# design.net
KiCad netlist of a schematic drawn in EasyEDA Pro
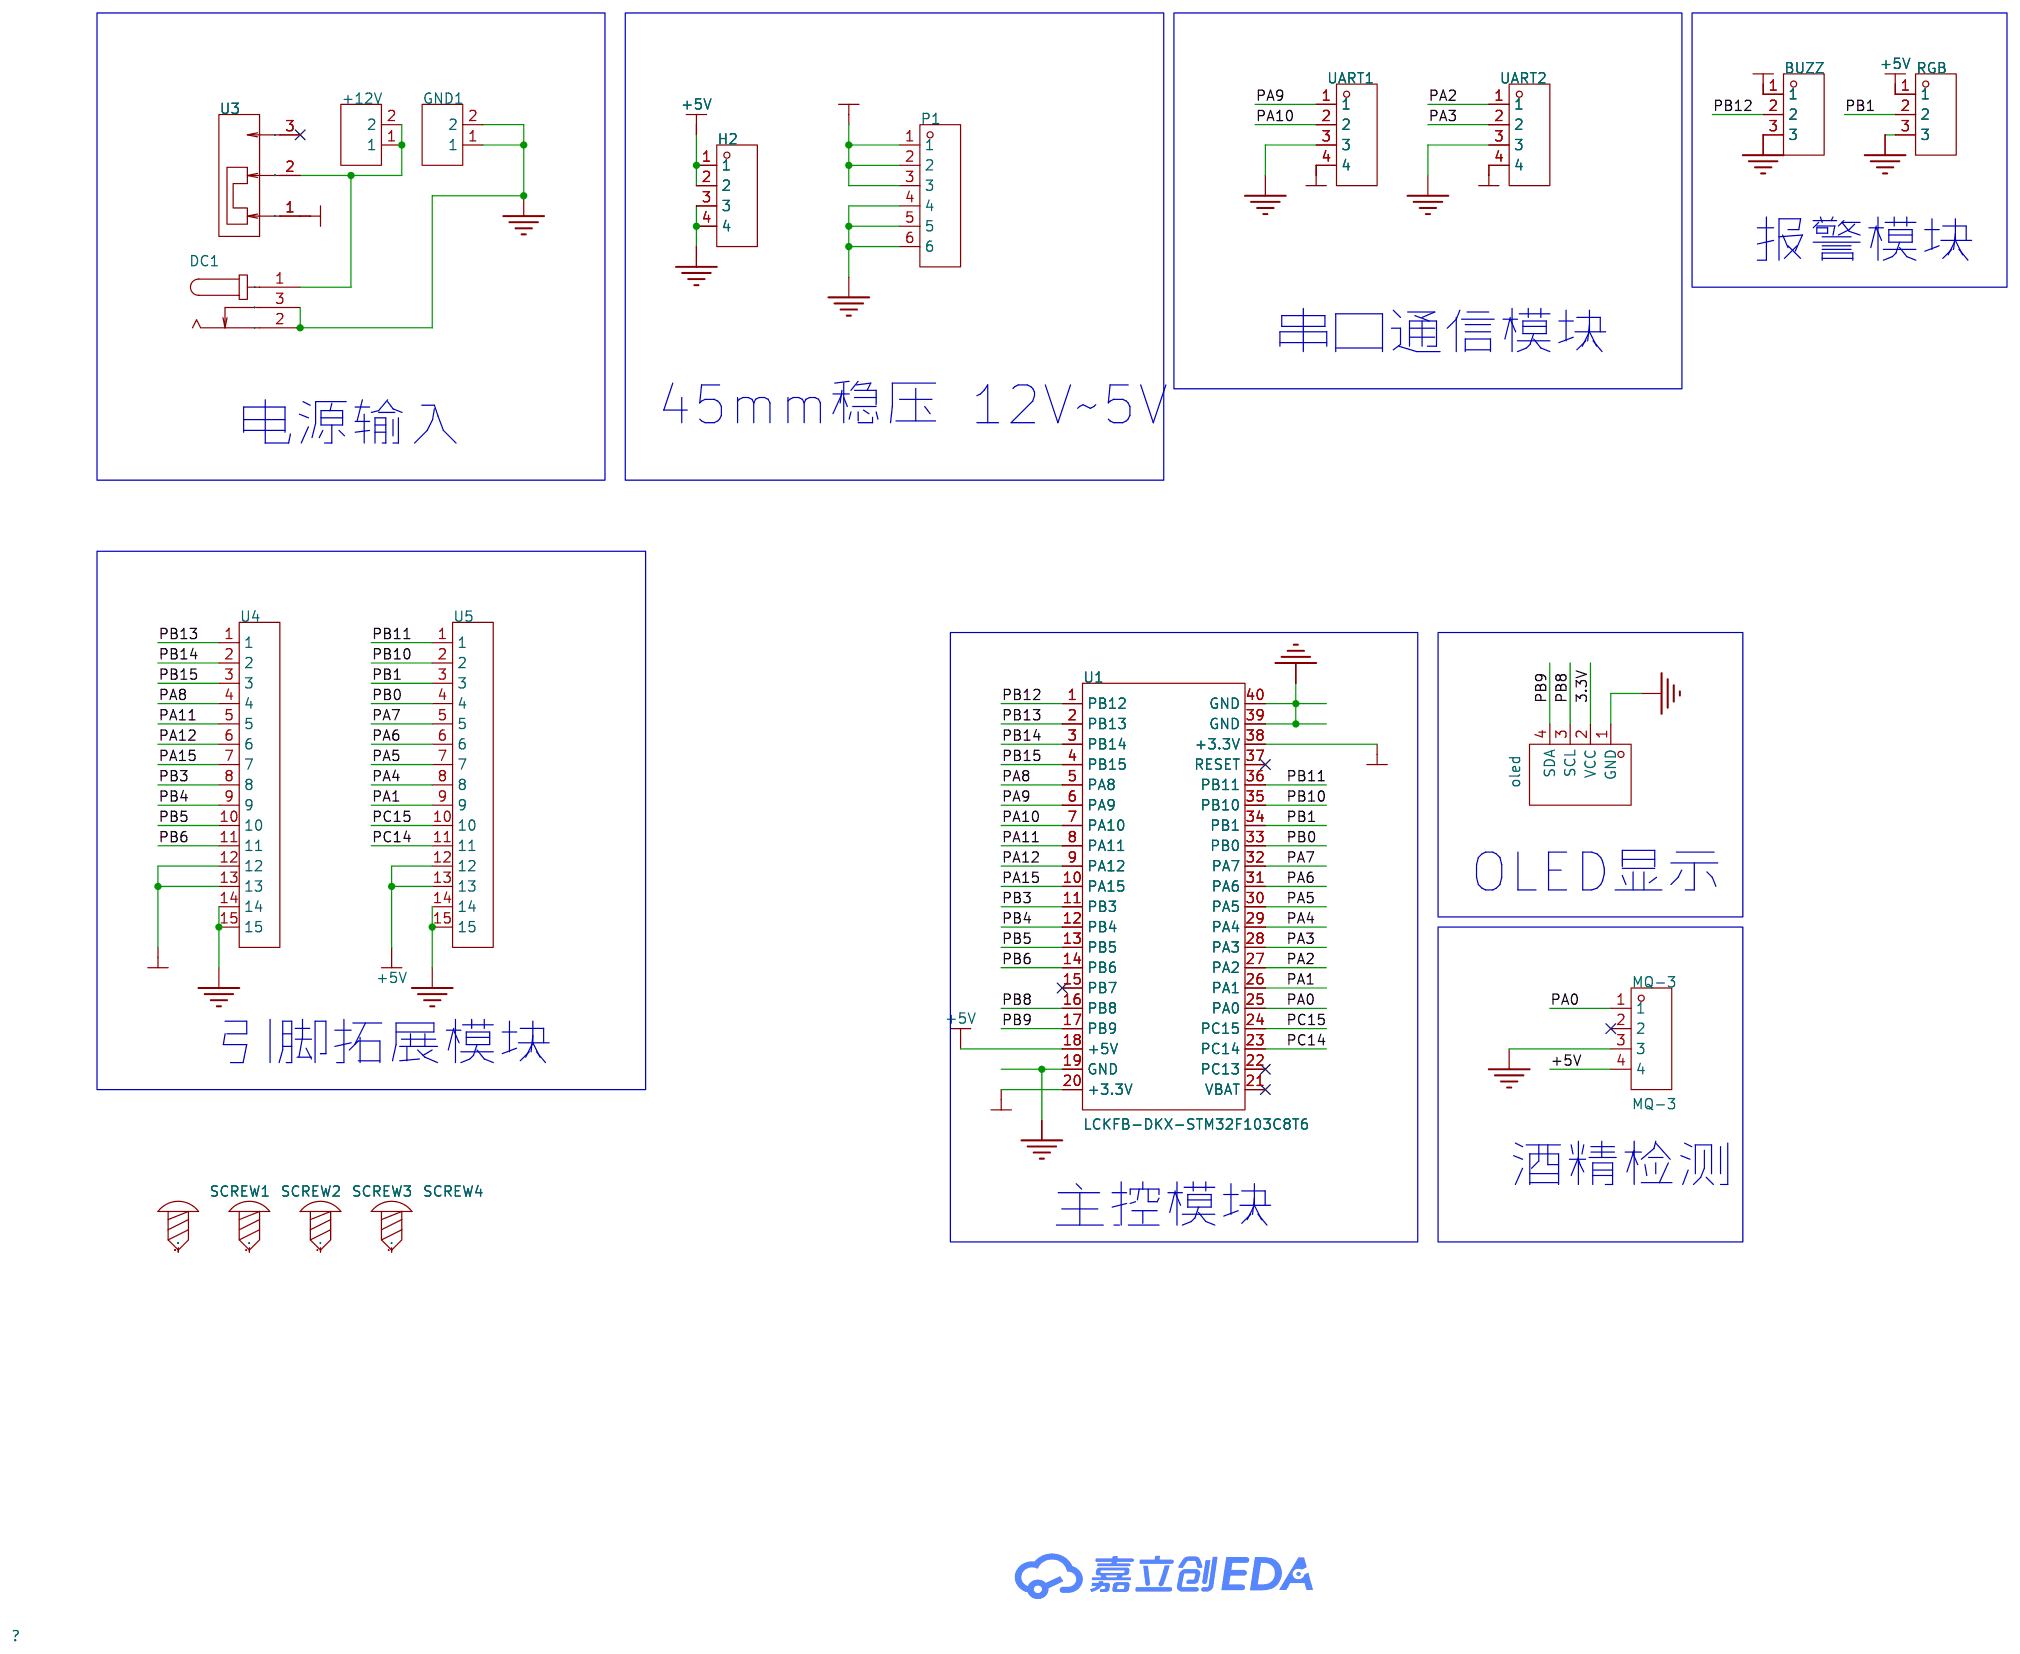
[diagram p0: schematic sheet]

(export (version "E")
  (design (tool "Eeschema 10.0.6"))
  (components
    (comp (ref "+12V")
      (value "Z-211-0211-0021-001")
      (footprint "easyedapro:HDR-TH_2P-P2.54-V-M-1")
      (fields (field (name "Manufacturer") "Nextron(正凌)"))
      (libsource (lib "easyedapro") (part "Z-211-0211-0021-001"))
    )
    (comp (ref "BUZZ")
      (value "HC-PM254-8.5H-1x3PZ-02A")
      (footprint "easyedapro:HDR-TH_3P-P2.54-V-F")
      (fields (field (name "Manufacturer") "HC(虹成电子)"))
      (libsource (lib "easyedapro") (part "HC-PM254-8.5H-1X3PZ"))
    )
    (comp (ref "DC1")
      (value "DC005-T")
      (footprint "easyedapro:DC-IN-TH_DC005-T")
      (description "连接器类型:DC电源插座;安装方式:弯插;触点内径:2mm;触点外径:6.3mm;额定电流:1.5A;额定电压:12V;工作温度:-30°C~+70°C;")
      (fields (field (name "Manufacturer") "SHOU HAN(首韩)"))
      (libsource (lib "easyedapro") (part "DC005-T"))
    )
    (comp (ref "GND1")
      (value "Z-211-0211-0021-001")
      (footprint "easyedapro:HDR-TH_2P-P2.54-V-M-1")
      (fields (field (name "Manufacturer") "Nextron(正凌)"))
      (libsource (lib "easyedapro") (part "Z-211-0211-0021-001"))
    )
    (comp (ref "H2")
      (value "2.54-1*4P母")
      (footprint "easyedapro:HDR-TH_4P-P2.54-V-F")
      (fields (field (name "Manufacturer") "BOOMELE(博穆精密)"))
      (libsource (lib "easyedapro") (part "2.54-1*4P母"))
    )
    (comp (ref "MQ-3")
      (value "MQ-3")
      (footprint "easyedapro:HDR-TH_4P-P2.54-V-F")
      (fields (field (name "Manufacturer") "XFCN(兴飞)"))
      (libsource (lib "easyedapro") (part "PM254V-11-04-H85"))
    )
    (comp (ref "oled")
      (value "HS96L03W2C03")
      (footprint "easyedapro:OLED-TH_L27.8-W27.2-P2.54_C9900033791")
      (description "主控芯片:SSD1315;接口类型:I2C;尺寸(inch):0.96;像素分辨率:128x64;")
      (fields (field (name "Manufacturer") "HS(汉昇)"))
      (libsource (lib "easyedapro") (part "HS96L03W2C03"))
    )
    (comp (ref "P1")
      (value "2.54-1*6P母")
      (footprint "easyedapro:HDR-TH_6P-P2.54-V-F")
      (fields (field (name "Manufacturer") "BOOMELE(博穆精密)"))
      (libsource (lib "easyedapro") (part "Header-Female-2.54_1x6"))
    )
    (comp (ref "RGB")
      (value "HC-PM254-8.5H-1x3PZ-02A")
      (footprint "easyedapro:HDR-TH_3P-P2.54-V-F")
      (fields (field (name "Manufacturer") "HC(虹成电子)"))
      (libsource (lib "easyedapro") (part "HC-PM254-8.5H-1X3PZ"))
    )
    (comp (ref "SCREW1")
      (value "~")
      (footprint "easyedapro:M2螺丝")
      (libsource (lib "easyedapro") (part "螺丝孔"))
    )
    (comp (ref "SCREW2")
      (value "~")
      (footprint "easyedapro:M2螺丝")
      (libsource (lib "easyedapro") (part "螺丝孔"))
    )
    (comp (ref "SCREW3")
      (value "~")
      (footprint "easyedapro:M2螺丝")
      (libsource (lib "easyedapro") (part "螺丝孔"))
    )
    (comp (ref "SCREW4")
      (value "~")
      (footprint "easyedapro:M2螺丝")
      (libsource (lib "easyedapro") (part "螺丝孔"))
    )
    (comp (ref "U1")
      (value "LCKFB-DKX-STM32F103C8T6")
      (footprint "easyedapro:CONN-TH_L53.3-W22.9_STM32F103C8T6-CARD")
      (description "搭载Contex M3内核,程序存储容量64KB,RAM总容量20KB,最高72MHz主频,提供高效的计算能力和稳定的运行环境。")
      (fields (field (name "Manufacturer") "立创开发板"))
      (libsource (lib "easyedapro") (part "LCKFB-DKX-STM32F103C8T6"))
    )
    (comp (ref "U3")
      (value "SS-12D10-G5")
      (footprint "easyedapro:SW-TH_SS-12D10-G050")
      (description "电路结构:单刀双掷;安装方式:直插;开关颜色:黑色;工作寿命:-;")
      (fields (field (name "Manufacturer") "DEALON(德艺隆)"))
      (libsource (lib "easyedapro") (part "SS-12D10-G5"))
    )
    (comp (ref "U4")
      (value "ZX-PZ2.54-1-15PZZ")
      (footprint "easyedapro:HDR-TH_15P-P2.54-V-M")
      (fields (field (name "Manufacturer") "Megastar(兆星)"))
      (libsource (lib "easyedapro") (part "ZX-PZ2.54-1-15PZZ"))
    )
    (comp (ref "U5")
      (value "ZX-PZ2.54-1-15PZZ")
      (footprint "easyedapro:HDR-TH_15P-P2.54-V-M")
      (fields (field (name "Manufacturer") "Megastar(兆星)"))
      (libsource (lib "easyedapro") (part "ZX-PZ2.54-1-15PZZ"))
    )
    (comp (ref "UART1")
      (value "PZ254V-11-04P")
      (footprint "easyedapro:HDR-TH_4P-P2.54-V-M")
      (fields (field (name "Manufacturer") "XFCN(兴飞)"))
      (libsource (lib "easyedapro") (part "PZ254V-11-04P_C2691448"))
    )
    (comp (ref "UART2")
      (value "PZ254V-11-04P")
      (footprint "easyedapro:HDR-TH_4P-P2.54-V-M")
      (fields (field (name "Manufacturer") "XFCN(兴飞)"))
      (libsource (lib "easyedapro") (part "PZ254V-11-04P_C2691448"))
    )
  )
  (nets
    (net (code "1") (name "+5V") (class "Default")
      (node (ref "H2") (pin "1") (pinfunction "1_1") (pintype "unspecified"))
      (node (ref "H2") (pin "2") (pinfunction "2_2") (pintype "unspecified"))
      (node (ref "MQ-3") (pin "4") (pinfunction "4_4") (pintype "unspecified"))
      (node (ref "RGB") (pin "1") (pinfunction "1_1") (pintype "unspecified"))
      (node (ref "U1") (pin "18") (pinfunction "+5V_18") (pintype "unspecified"))
      (node (ref "U5") (pin "12") (pinfunction "12_12") (pintype "unspecified"))
      (node (ref "U5") (pin "13") (pinfunction "13_13") (pintype "unspecified"))
    )
    (net (code "2") (name "+12V") (class "Default")
      (node (ref "P1") (pin "1") (pinfunction "1_1") (pintype "unspecified"))
      (node (ref "P1") (pin "2") (pinfunction "2_2") (pintype "unspecified"))
      (node (ref "P1") (pin "3") (pinfunction "3_3") (pintype "unspecified"))
      (node (ref "U3") (pin "1") (pinfunction "1_1") (pintype "unspecified"))
    )
    (net (code "3") (name "/PA0") (class "Default")
      (node (ref "MQ-3") (pin "1") (pinfunction "1_1") (pintype "unspecified"))
      (node (ref "U1") (pin "25") (pinfunction "PA0_25") (pintype "unspecified"))
    )
    (net (code "4") (name "/PA1") (class "Default")
      (node (ref "U1") (pin "26") (pinfunction "PA1_26") (pintype "unspecified"))
      (node (ref "U5") (pin "9") (pinfunction "9_9") (pintype "unspecified"))
    )
    (net (code "5") (name "/PA2") (class "Default")
      (node (ref "U1") (pin "27") (pinfunction "PA2_27") (pintype "unspecified"))
      (node (ref "UART2") (pin "1") (pinfunction "1_1") (pintype "unspecified"))
    )
    (net (code "6") (name "/PA3") (class "Default")
      (node (ref "U1") (pin "28") (pinfunction "PA3_28") (pintype "unspecified"))
      (node (ref "UART2") (pin "2") (pinfunction "2_2") (pintype "unspecified"))
    )
    (net (code "7") (name "/PA4") (class "Default")
      (node (ref "U1") (pin "29") (pinfunction "PA4_29") (pintype "unspecified"))
      (node (ref "U5") (pin "8") (pinfunction "8_8") (pintype "unspecified"))
    )
    (net (code "8") (name "/PA5") (class "Default")
      (node (ref "U1") (pin "30") (pinfunction "PA5_30") (pintype "unspecified"))
      (node (ref "U5") (pin "7") (pinfunction "7_7") (pintype "unspecified"))
    )
    (net (code "9") (name "/PA6") (class "Default")
      (node (ref "U1") (pin "31") (pinfunction "PA6_31") (pintype "unspecified"))
      (node (ref "U5") (pin "6") (pinfunction "6_6") (pintype "unspecified"))
    )
    (net (code "10") (name "/PA7") (class "Default")
      (node (ref "U1") (pin "32") (pinfunction "PA7_32") (pintype "unspecified"))
      (node (ref "U5") (pin "5") (pinfunction "5_5") (pintype "unspecified"))
    )
    (net (code "11") (name "/PA8") (class "Default")
      (node (ref "U1") (pin "5") (pinfunction "PA8_5") (pintype "unspecified"))
      (node (ref "U4") (pin "4") (pinfunction "4_4") (pintype "unspecified"))
    )
    (net (code "12") (name "/PA9") (class "Default")
      (node (ref "U1") (pin "6") (pinfunction "PA9_6") (pintype "unspecified"))
      (node (ref "UART1") (pin "1") (pinfunction "1_1") (pintype "unspecified"))
    )
    (net (code "13") (name "/PA10") (class "Default")
      (node (ref "U1") (pin "7") (pinfunction "PA10_7") (pintype "unspecified"))
      (node (ref "UART1") (pin "2") (pinfunction "2_2") (pintype "unspecified"))
    )
    (net (code "14") (name "/PA11") (class "Default")
      (node (ref "U1") (pin "8") (pinfunction "PA11_8") (pintype "unspecified"))
      (node (ref "U4") (pin "5") (pinfunction "5_5") (pintype "unspecified"))
    )
    (net (code "15") (name "/PA12") (class "Default")
      (node (ref "U1") (pin "9") (pinfunction "PA12_9") (pintype "unspecified"))
      (node (ref "U4") (pin "6") (pinfunction "6_6") (pintype "unspecified"))
    )
    (net (code "16") (name "/PA15") (class "Default")
      (node (ref "U1") (pin "10") (pinfunction "PA15_10") (pintype "unspecified"))
      (node (ref "U4") (pin "7") (pinfunction "7_7") (pintype "unspecified"))
    )
    (net (code "17") (name "/PB0") (class "Default")
      (node (ref "U1") (pin "33") (pinfunction "PB0_33") (pintype "unspecified"))
      (node (ref "U5") (pin "4") (pinfunction "4_4") (pintype "unspecified"))
    )
    (net (code "18") (name "/PB1") (class "Default")
      (node (ref "RGB") (pin "2") (pinfunction "2_2") (pintype "unspecified"))
      (node (ref "U1") (pin "34") (pinfunction "PB1_34") (pintype "unspecified"))
      (node (ref "U5") (pin "3") (pinfunction "3_3") (pintype "unspecified"))
    )
    (net (code "19") (name "/PB3") (class "Default")
      (node (ref "U1") (pin "11") (pinfunction "PB3_11") (pintype "unspecified"))
      (node (ref "U4") (pin "8") (pinfunction "8_8") (pintype "unspecified"))
    )
    (net (code "20") (name "/PB4") (class "Default")
      (node (ref "U1") (pin "12") (pinfunction "PB4_12") (pintype "unspecified"))
      (node (ref "U4") (pin "9") (pinfunction "9_9") (pintype "unspecified"))
    )
    (net (code "21") (name "/PB5") (class "Default")
      (node (ref "U1") (pin "13") (pinfunction "PB5_13") (pintype "unspecified"))
      (node (ref "U4") (pin "10") (pinfunction "10_10") (pintype "unspecified"))
    )
    (net (code "22") (name "/PB6") (class "Default")
      (node (ref "U1") (pin "14") (pinfunction "PB6_14") (pintype "unspecified"))
      (node (ref "U4") (pin "11") (pinfunction "11_11") (pintype "unspecified"))
    )
    (net (code "23") (name "/PB8") (class "Default")
      (node (ref "U1") (pin "16") (pinfunction "PB8_16") (pintype "unspecified"))
      (node (ref "oled") (pin "3") (pinfunction "SCL_3") (pintype "unspecified"))
    )
    (net (code "24") (name "/PB9") (class "Default")
      (node (ref "U1") (pin "17") (pinfunction "PB9_17") (pintype "unspecified"))
      (node (ref "oled") (pin "4") (pinfunction "SDA_4") (pintype "unspecified"))
    )
    (net (code "25") (name "/PB10") (class "Default")
      (node (ref "U1") (pin "35") (pinfunction "PB10_35") (pintype "unspecified"))
      (node (ref "U5") (pin "2") (pinfunction "2_2") (pintype "unspecified"))
    )
    (net (code "26") (name "/PB11") (class "Default")
      (node (ref "U1") (pin "36") (pinfunction "PB11_36") (pintype "unspecified"))
      (node (ref "U5") (pin "1") (pinfunction "1_1") (pintype "unspecified"))
    )
    (net (code "27") (name "/PB12") (class "Default")
      (node (ref "BUZZ") (pin "2") (pinfunction "2_2") (pintype "unspecified"))
      (node (ref "U1") (pin "1") (pinfunction "PB12_1") (pintype "unspecified"))
    )
    (net (code "28") (name "/PB13") (class "Default")
      (node (ref "U1") (pin "2") (pinfunction "PB13_2") (pintype "unspecified"))
      (node (ref "U4") (pin "1") (pinfunction "1_1") (pintype "unspecified"))
    )
    (net (code "29") (name "/PB14") (class "Default")
      (node (ref "U1") (pin "3") (pinfunction "PB14_3") (pintype "unspecified"))
      (node (ref "U4") (pin "2") (pinfunction "2_2") (pintype "unspecified"))
    )
    (net (code "30") (name "/PB15") (class "Default")
      (node (ref "U1") (pin "4") (pinfunction "PB15_4") (pintype "unspecified"))
      (node (ref "U4") (pin "3") (pinfunction "3_3") (pintype "unspecified"))
    )
    (net (code "31") (name "/PC14") (class "Default")
      (node (ref "U1") (pin "23") (pinfunction "PC14_23") (pintype "unspecified"))
      (node (ref "U5") (pin "11") (pinfunction "11_11") (pintype "unspecified"))
    )
    (net (code "32") (name "/PC15") (class "Default")
      (node (ref "U1") (pin "24") (pinfunction "PC15_24") (pintype "unspecified"))
      (node (ref "U5") (pin "10") (pinfunction "10_10") (pintype "unspecified"))
    )
    (net (code "33") (name "3.3V") (class "Default")
      (node (ref "BUZZ") (pin "1") (pinfunction "1_1") (pintype "unspecified"))
      (node (ref "U1") (pin "20") (pinfunction "+3.3V_20") (pintype "unspecified"))
      (node (ref "U1") (pin "38") (pinfunction "+3.3V_38") (pintype "unspecified"))
      (node (ref "U4") (pin "12") (pinfunction "12_12") (pintype "unspecified"))
      (node (ref "U4") (pin "13") (pinfunction "13_13") (pintype "unspecified"))
      (node (ref "UART1") (pin "4") (pinfunction "4_4") (pintype "unspecified"))
      (node (ref "UART2") (pin "4") (pinfunction "4_4") (pintype "unspecified"))
      (node (ref "oled") (pin "2") (pinfunction "VCC_2") (pintype "unspecified"))
    )
    (net (code "34") (name "GND") (class "Default")
      (node (ref "BUZZ") (pin "3") (pinfunction "3_3") (pintype "unspecified"))
      (node (ref "DC1") (pin "2") (pinfunction "2_2") (pintype "unspecified"))
      (node (ref "DC1") (pin "3") (pinfunction "3_3") (pintype "unspecified"))
      (node (ref "GND1") (pin "1") (pinfunction "1_1") (pintype "unspecified"))
      (node (ref "GND1") (pin "2") (pinfunction "2_2") (pintype "unspecified"))
      (node (ref "H2") (pin "3") (pinfunction "3_3") (pintype "unspecified"))
      (node (ref "H2") (pin "4") (pinfunction "4_4") (pintype "unspecified"))
      (node (ref "MQ-3") (pin "3") (pinfunction "3_3") (pintype "unspecified"))
      (node (ref "P1") (pin "4") (pinfunction "4_4") (pintype "unspecified"))
      (node (ref "P1") (pin "5") (pinfunction "5_5") (pintype "unspecified"))
      (node (ref "P1") (pin "6") (pinfunction "6_6") (pintype "unspecified"))
      (node (ref "RGB") (pin "3") (pinfunction "3_3") (pintype "unspecified"))
      (node (ref "U1") (pin "19") (pinfunction "GND_19") (pintype "unspecified"))
      (node (ref "U1") (pin "39") (pinfunction "GND_39") (pintype "unspecified"))
      (node (ref "U1") (pin "40") (pinfunction "GND_40") (pintype "unspecified"))
      (node (ref "U4") (pin "14") (pinfunction "14_14") (pintype "unspecified"))
      (node (ref "U4") (pin "15") (pinfunction "15_15") (pintype "unspecified"))
      (node (ref "U5") (pin "14") (pinfunction "14_14") (pintype "unspecified"))
      (node (ref "U5") (pin "15") (pinfunction "15_15") (pintype "unspecified"))
      (node (ref "UART1") (pin "3") (pinfunction "3_3") (pintype "unspecified"))
      (node (ref "UART2") (pin "3") (pinfunction "3_3") (pintype "unspecified"))
      (node (ref "oled") (pin "1") (pinfunction "GND_1") (pintype "unspecified"))
    )
    (net (code "35") (name "Net-(+12V-Pad1)") (class "Default")
      (node (ref "+12V") (pin "1") (pinfunction "1_1") (pintype "unspecified"))
      (node (ref "+12V") (pin "2") (pinfunction "2_2") (pintype "unspecified"))
      (node (ref "DC1") (pin "1") (pinfunction "1_1") (pintype "unspecified"))
      (node (ref "U3") (pin "2") (pinfunction "2_2") (pintype "unspecified"))
    )
    (net (code "36") (name "unconnected-(MQ-3-Pad2)") (class "Default")
      (node (ref "MQ-3") (pin "2") (pinfunction "2_2") (pintype "unspecified+no_connect"))
    )
    (net (code "37") (name "unconnected-(SCREW1-Pad1)") (class "Default")
      (node (ref "SCREW1") (pin "1") (pinfunction "1_1") (pintype "input"))
    )
    (net (code "38") (name "unconnected-(SCREW2-Pad1)") (class "Default")
      (node (ref "SCREW2") (pin "1") (pinfunction "1_1") (pintype "input"))
    )
    (net (code "39") (name "unconnected-(SCREW3-Pad1)") (class "Default")
      (node (ref "SCREW3") (pin "1") (pinfunction "1_1") (pintype "input"))
    )
    (net (code "40") (name "unconnected-(SCREW4-Pad1)") (class "Default")
      (node (ref "SCREW4") (pin "1") (pinfunction "1_1") (pintype "input"))
    )
    (net (code "41") (name "unconnected-(U1-PB7-Pad15)") (class "Default")
      (node (ref "U1") (pin "15") (pinfunction "PB7_15") (pintype "unspecified+no_connect"))
    )
    (net (code "42") (name "unconnected-(U1-PC13-Pad22)") (class "Default")
      (node (ref "U1") (pin "22") (pinfunction "PC13_22") (pintype "unspecified+no_connect"))
    )
    (net (code "43") (name "unconnected-(U1-RESET-Pad37)") (class "Default")
      (node (ref "U1") (pin "37") (pinfunction "RESET_37") (pintype "unspecified+no_connect"))
    )
    (net (code "44") (name "unconnected-(U1-VBAT-Pad21)") (class "Default")
      (node (ref "U1") (pin "21") (pinfunction "VBAT_21") (pintype "unspecified+no_connect"))
    )
    (net (code "45") (name "unconnected-(U3-Pad3)") (class "Default")
      (node (ref "U3") (pin "3") (pinfunction "3_3") (pintype "unspecified+no_connect"))
    )
  )
)
